# HYDRA_V4_RECOVERY.net
KiCad netlist of a schematic drawn in Altium Designer
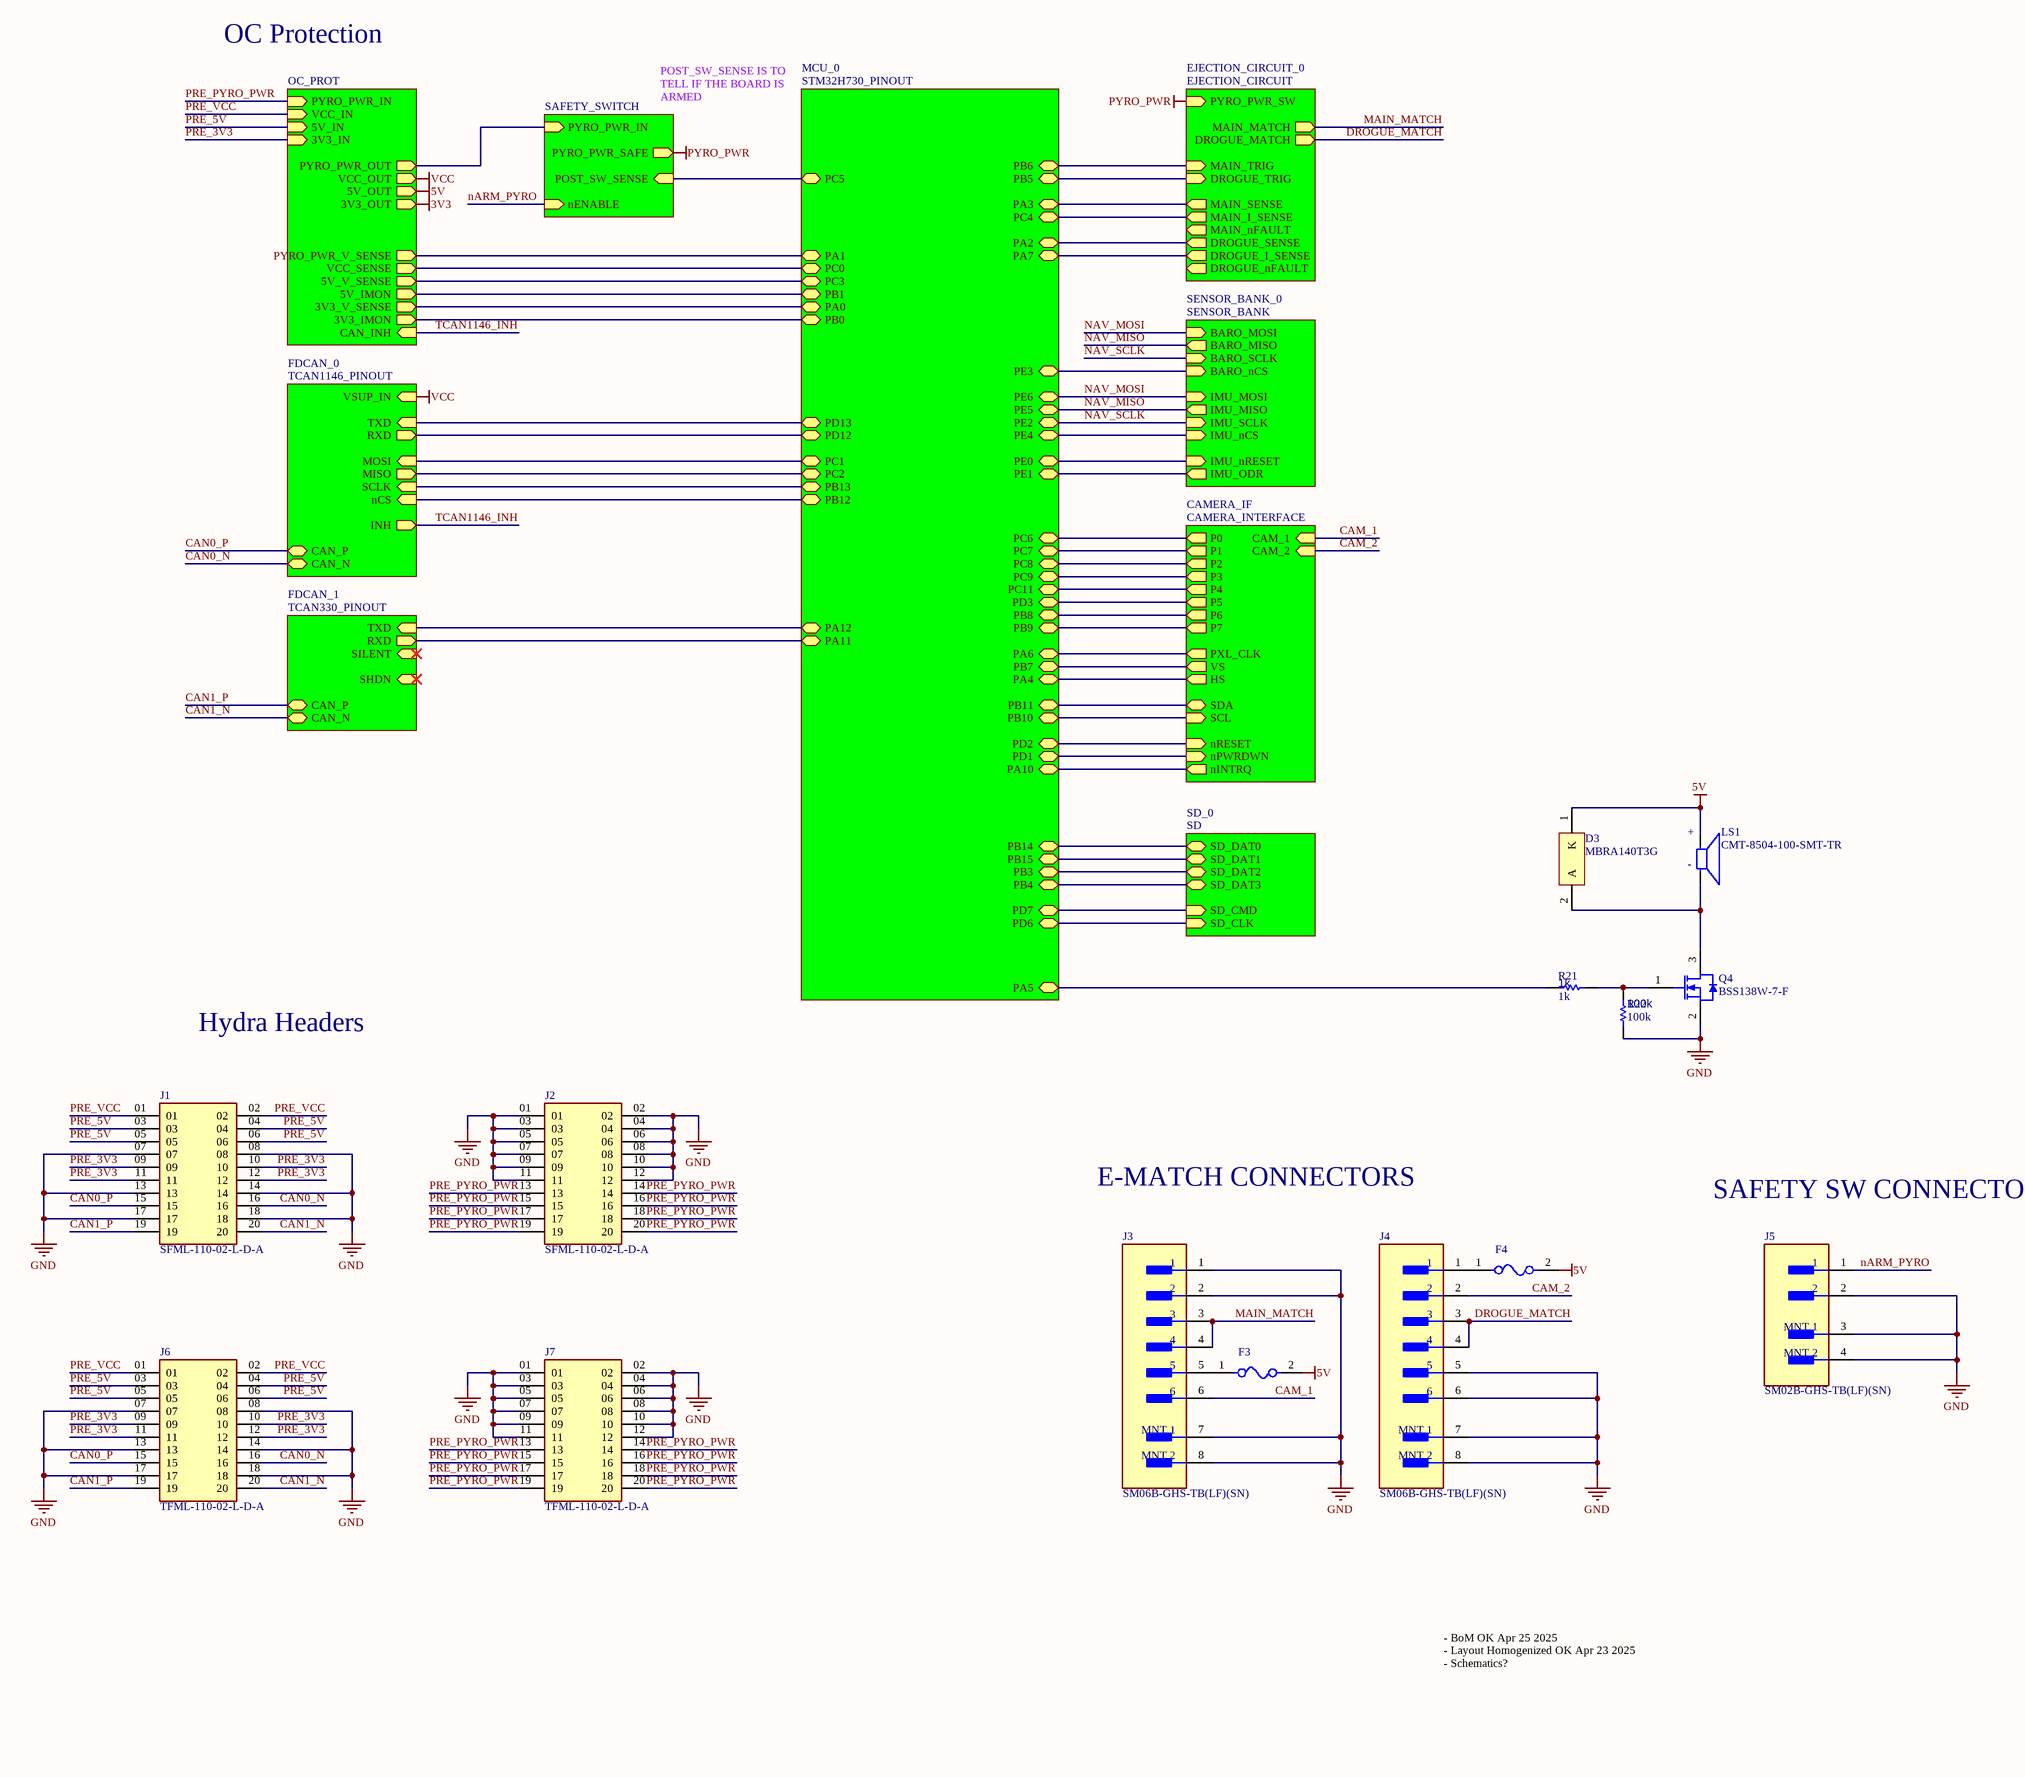
[diagram p0: HYDRA_V4_RECOVERY.SchDoc]

(export (version "E")
  (design (tool "Eeschema 10.0.6"))
  (components
    (comp (ref "D3")
      (value "MBRA140T3G")
      (footprint "ONSC-SMA-2-403D-02_V")
      (description "Schottky Power Rectifier, 2-Pin SMA, Pb-Free, Tape and Reel")
      (fields (field (name "MANUFACTURER") "On Semiconductor"))
      (libsource (lib "Altium Content Vault") (part "ONSC-D-K1A2-2_A"))
    )
    (comp (ref "F3")
      (value "MF-FSMF050X-2")
      (footprint "FP-MF-FSMF-MFG")
      (description "PTC RESET FUSE 6V 500MA 0603")
      (fields
        (field (name "MANUFACTURER") "Bourns Inc.")
        (field (name "OCTOPART") "https://octopart.com/mf-fsmf050x-2-bourns-10470804")
      )
      (libsource (lib "Altium Content Vault") (part "5bcf9b9f640e542cf0359d10258e979"))
    )
    (comp (ref "F4")
      (value "MF-FSMF050X-2")
      (footprint "FP-MF-FSMF-MFG")
      (description "PTC RESET FUSE 6V 500MA 0603")
      (fields
        (field (name "MANUFACTURER") "Bourns Inc.")
        (field (name "OCTOPART") "https://octopart.com/mf-fsmf050x-2-bourns-10470804")
      )
      (libsource (lib "Altium Content Vault") (part "5bcf9b9f640e542cf0359d10258e979"))
    )
    (comp (ref "J1")
      (value "SFML-110-02-L-D-A")
      (footprint "SFML-110-02-L-D-A-Footprint-1")
      (libsource (lib "Space Concordia") (part "SFML-110-02-L-D-A"))
    )
    (comp (ref "J2")
      (value "SFML-110-02-L-D-A")
      (footprint "SFML-110-02-L-D-A-Footprint-1")
      (libsource (lib "Space Concordia") (part "SFML-110-02-L-D-A"))
    )
    (comp (ref "J3")
      (value "SM06B-GHS-TB(LF)(SN)")
      (footprint "FP-SM06B-GHS-TB_LF_SN-MFG")
      (description "Conn Shrouded Header HDR 6 POS 1.25mm Solder RA Side Entry SMD T/R")
      (libsource (lib "Space Concordia") (part "ed24c53d9ba001d1a2a686240a95171"))
    )
    (comp (ref "J4")
      (value "SM06B-GHS-TB(LF)(SN)")
      (footprint "FP-SM06B-GHS-TB_LF_SN-MFG")
      (description "Conn Shrouded Header HDR 6 POS 1.25mm Solder RA Side Entry SMD T/R")
      (libsource (lib "Space Concordia") (part "ed24c53d9ba001d1a2a686240a95171"))
    )
    (comp (ref "J5")
      (value "SM02B-GHS-TB(LF)(SN)")
      (footprint "FP-SM02B-GHS-TB_LF_SN-MFG")
      (description "MCU 32-bit LPC1800 ARM Cortex M3 RISC 768KB Flash 3.3V 100-Pin TFBGA Tray")
      (libsource (lib "Space Concordia") (part "56ec3178a87b3978bdc1b3682cd516a"))
    )
    (comp (ref "J6")
      (value "TFML-110-02-L-D-A")
      (footprint "TFML-110-02-L-D-A-Footprint-1")
      (description "Board Connector, 20 Contact(s), 2 Row(s), Male, Straight, Surface Mount Terminal")
      (libsource (lib "Space Concordia") (part "TFML-110-02-L-D-A"))
    )
    (comp (ref "J7")
      (value "TFML-110-02-L-D-A")
      (footprint "TFML-110-02-L-D-A-Footprint-1")
      (description "Board Connector, 20 Contact(s), 2 Row(s), Male, Straight, Surface Mount Terminal")
      (libsource (lib "Space Concordia") (part "TFML-110-02-L-D-A"))
    )
    (comp (ref "LS1")
      (value "CMT-8504-100-SMT-TR")
      (footprint "CMT-8504-100-SMT-TR-Footprint-1")
      (description "8.5 mm, 5 Vo-p, 100 dB, Surface Mount (SMT), Magnetic Audio Transducer Buzzer")
      (libsource (lib "Space Concordia") (part "CMT-8504-100-SMT-TR"))
    )
    (comp (ref "Q4")
      (value "BSS138W-7-F")
      (footprint "DIOD-SOT323-3_V")
      (fields (field (name "MANUFACTURER") "DiodesIncorporated"))
      (libsource (lib "Altium Content Vault") (part "NEMOS-GSD-3"))
    )
    (comp (ref "R21")
      (value "1k")
      (footprint "R0603B")
      (description "Resistor")
      (fields (field (name "ALTIUM_VALUE") "1k"))
      (libsource (lib "Space Concordia") (part "Resistor"))
    )
    (comp (ref "R22")
      (value "100k")
      (footprint "R0603B")
      (description "Resistor")
      (fields (field (name "ALTIUM_VALUE") "100k"))
      (libsource (lib "Space Concordia") (part "Resistor"))
    )
  )
  (nets
    (net (code "6") (name "/CAM_1") (class "Default")
      (node (ref "J3") (pin "6") (pinfunction "6_6") (pintype "passive"))
    )
    (net (code "7") (name "/CAM_2") (class "Default")
      (node (ref "J4") (pin "2") (pinfunction "2_2") (pintype "passive"))
    )
    (net (code "8") (name "/CAN0_N") (class "Default")
      (node (ref "J1") (pin "16") (pinfunction "16_16") (pintype "passive"))
      (node (ref "J6") (pin "16") (pinfunction "16_16") (pintype "passive"))
    )
    (net (code "9") (name "/CAN0_P") (class "Default")
      (node (ref "J1") (pin "15") (pinfunction "15_15") (pintype "passive"))
      (node (ref "J6") (pin "15") (pinfunction "15_15") (pintype "passive"))
    )
    (net (code "10") (name "/CAN1_N") (class "Default")
      (node (ref "J1") (pin "20") (pinfunction "20_20") (pintype "passive"))
      (node (ref "J6") (pin "20") (pinfunction "20_20") (pintype "passive"))
    )
    (net (code "11") (name "/CAN1_P") (class "Default")
      (node (ref "J1") (pin "19") (pinfunction "19_19") (pintype "passive"))
      (node (ref "J6") (pin "19") (pinfunction "19_19") (pintype "passive"))
    )
    (net (code "13") (name "/DROGUE_MATCH") (class "Default")
      (node (ref "J4") (pin "3") (pinfunction "3_3") (pintype "passive"))
      (node (ref "J4") (pin "4") (pinfunction "4_4") (pintype "passive"))
    )
    (net (code "22") (name "/MAIN_MATCH") (class "Default")
      (node (ref "J3") (pin "3") (pinfunction "3_3") (pintype "passive"))
      (node (ref "J3") (pin "4") (pinfunction "4_4") (pintype "passive"))
    )
    (net (code "39") (name "/PA5") (class "Default")
      (node (ref "R21") (pin "2") (pinfunction "2_2") (pintype "passive"))
    )
    (net (code "55") (name "/PRE_3V3") (class "Default")
      (node (ref "J1") (pin "09") (pinfunction "09_09") (pintype "passive"))
      (node (ref "J1") (pin "10") (pinfunction "10_10") (pintype "passive"))
      (node (ref "J1") (pin "11") (pinfunction "11_11") (pintype "passive"))
      (node (ref "J1") (pin "12") (pinfunction "12_12") (pintype "passive"))
      (node (ref "J6") (pin "09") (pinfunction "09_09") (pintype "passive"))
      (node (ref "J6") (pin "10") (pinfunction "10_10") (pintype "passive"))
      (node (ref "J6") (pin "11") (pinfunction "11_11") (pintype "passive"))
      (node (ref "J6") (pin "12") (pinfunction "12_12") (pintype "passive"))
    )
    (net (code "56") (name "/PRE_5V") (class "Default")
      (node (ref "J1") (pin "03") (pinfunction "03_03") (pintype "passive"))
      (node (ref "J1") (pin "04") (pinfunction "04_04") (pintype "passive"))
      (node (ref "J1") (pin "05") (pinfunction "05_05") (pintype "passive"))
      (node (ref "J1") (pin "06") (pinfunction "06_06") (pintype "passive"))
      (node (ref "J6") (pin "03") (pinfunction "03_03") (pintype "passive"))
      (node (ref "J6") (pin "04") (pinfunction "04_04") (pintype "passive"))
      (node (ref "J6") (pin "05") (pinfunction "05_05") (pintype "passive"))
      (node (ref "J6") (pin "06") (pinfunction "06_06") (pintype "passive"))
    )
    (net (code "57") (name "/PRE_PYRO_PWR") (class "Default")
      (node (ref "J2") (pin "13") (pinfunction "13_13") (pintype "passive"))
      (node (ref "J2") (pin "14") (pinfunction "14_14") (pintype "passive"))
      (node (ref "J2") (pin "15") (pinfunction "15_15") (pintype "passive"))
      (node (ref "J2") (pin "16") (pinfunction "16_16") (pintype "passive"))
      (node (ref "J2") (pin "17") (pinfunction "17_17") (pintype "passive"))
      (node (ref "J2") (pin "18") (pinfunction "18_18") (pintype "passive"))
      (node (ref "J2") (pin "19") (pinfunction "19_19") (pintype "passive"))
      (node (ref "J2") (pin "20") (pinfunction "20_20") (pintype "passive"))
      (node (ref "J7") (pin "13") (pinfunction "13_13") (pintype "passive"))
      (node (ref "J7") (pin "14") (pinfunction "14_14") (pintype "passive"))
      (node (ref "J7") (pin "15") (pinfunction "15_15") (pintype "passive"))
      (node (ref "J7") (pin "16") (pinfunction "16_16") (pintype "passive"))
      (node (ref "J7") (pin "17") (pinfunction "17_17") (pintype "passive"))
      (node (ref "J7") (pin "18") (pinfunction "18_18") (pintype "passive"))
      (node (ref "J7") (pin "19") (pinfunction "19_19") (pintype "passive"))
      (node (ref "J7") (pin "20") (pinfunction "20_20") (pintype "passive"))
    )
    (net (code "58") (name "/PRE_VCC") (class "Default")
      (node (ref "J1") (pin "01") (pinfunction "01_01") (pintype "passive"))
      (node (ref "J1") (pin "02") (pinfunction "02_02") (pintype "passive"))
      (node (ref "J6") (pin "01") (pinfunction "01_01") (pintype "passive"))
      (node (ref "J6") (pin "02") (pinfunction "02_02") (pintype "passive"))
    )
    (net (code "69") (name "/nARM_PYRO") (class "Default")
      (node (ref "J5") (pin "1") (pinfunction "1_1") (pintype "passive"))
    )
    (net (code "72") (name "5V") (class "Default")
      (node (ref "D3") (pin "1") (pinfunction "K_1") (pintype "passive"))
      (node (ref "F3") (pin "2") (pinfunction "2_2") (pintype "passive"))
      (node (ref "F4") (pin "2") (pinfunction "2_2") (pintype "passive"))
      (node (ref "LS1") (pin "P") (pinfunction "P_P") (pintype "passive"))
    )
    (net (code "73") (name "GND") (class "Default")
      (node (ref "J1") (pin "07") (pinfunction "07_07") (pintype "passive"))
      (node (ref "J1") (pin "08") (pinfunction "08_08") (pintype "passive"))
      (node (ref "J1") (pin "13") (pinfunction "13_13") (pintype "passive"))
      (node (ref "J1") (pin "14") (pinfunction "14_14") (pintype "passive"))
      (node (ref "J1") (pin "17") (pinfunction "17_17") (pintype "passive"))
      (node (ref "J1") (pin "18") (pinfunction "18_18") (pintype "passive"))
      (node (ref "J2") (pin "01") (pinfunction "01_01") (pintype "passive"))
      (node (ref "J2") (pin "02") (pinfunction "02_02") (pintype "passive"))
      (node (ref "J2") (pin "03") (pinfunction "03_03") (pintype "passive"))
      (node (ref "J2") (pin "04") (pinfunction "04_04") (pintype "passive"))
      (node (ref "J2") (pin "05") (pinfunction "05_05") (pintype "passive"))
      (node (ref "J2") (pin "06") (pinfunction "06_06") (pintype "passive"))
      (node (ref "J2") (pin "07") (pinfunction "07_07") (pintype "passive"))
      (node (ref "J2") (pin "08") (pinfunction "08_08") (pintype "passive"))
      (node (ref "J2") (pin "09") (pinfunction "09_09") (pintype "passive"))
      (node (ref "J2") (pin "10") (pinfunction "10_10") (pintype "passive"))
      (node (ref "J2") (pin "11") (pinfunction "11_11") (pintype "passive"))
      (node (ref "J2") (pin "12") (pinfunction "12_12") (pintype "passive"))
      (node (ref "J3") (pin "1") (pinfunction "1_1") (pintype "passive"))
      (node (ref "J3") (pin "2") (pinfunction "2_2") (pintype "passive"))
      (node (ref "J3") (pin "7") (pinfunction "MNT_1_7") (pintype "passive"))
      (node (ref "J3") (pin "8") (pinfunction "MNT_2_8") (pintype "passive"))
      (node (ref "J4") (pin "5") (pinfunction "5_5") (pintype "passive"))
      (node (ref "J4") (pin "6") (pinfunction "6_6") (pintype "passive"))
      (node (ref "J4") (pin "7") (pinfunction "MNT_1_7") (pintype "passive"))
      (node (ref "J4") (pin "8") (pinfunction "MNT_2_8") (pintype "passive"))
      (node (ref "J5") (pin "2") (pinfunction "2_2") (pintype "passive"))
      (node (ref "J5") (pin "3") (pinfunction "MNT_1_3") (pintype "passive"))
      (node (ref "J5") (pin "4") (pinfunction "MNT_2_4") (pintype "passive"))
      (node (ref "J6") (pin "07") (pinfunction "07_07") (pintype "passive"))
      (node (ref "J6") (pin "08") (pinfunction "08_08") (pintype "passive"))
      (node (ref "J6") (pin "13") (pinfunction "13_13") (pintype "passive"))
      (node (ref "J6") (pin "14") (pinfunction "14_14") (pintype "passive"))
      (node (ref "J6") (pin "17") (pinfunction "17_17") (pintype "passive"))
      (node (ref "J6") (pin "18") (pinfunction "18_18") (pintype "passive"))
      (node (ref "J7") (pin "01") (pinfunction "01_01") (pintype "passive"))
      (node (ref "J7") (pin "02") (pinfunction "02_02") (pintype "passive"))
      (node (ref "J7") (pin "03") (pinfunction "03_03") (pintype "passive"))
      (node (ref "J7") (pin "04") (pinfunction "04_04") (pintype "passive"))
      (node (ref "J7") (pin "05") (pinfunction "05_05") (pintype "passive"))
      (node (ref "J7") (pin "06") (pinfunction "06_06") (pintype "passive"))
      (node (ref "J7") (pin "07") (pinfunction "07_07") (pintype "passive"))
      (node (ref "J7") (pin "08") (pinfunction "08_08") (pintype "passive"))
      (node (ref "J7") (pin "09") (pinfunction "09_09") (pintype "passive"))
      (node (ref "J7") (pin "10") (pinfunction "10_10") (pintype "passive"))
      (node (ref "J7") (pin "11") (pinfunction "11_11") (pintype "passive"))
      (node (ref "J7") (pin "12") (pinfunction "12_12") (pintype "passive"))
      (node (ref "Q4") (pin "2") (pinfunction "S_2") (pintype "passive"))
      (node (ref "R22") (pin "2") (pinfunction "2_2") (pintype "passive"))
    )
    (net (code "74") (name "Net-(D3-A)") (class "Default")
      (node (ref "D3") (pin "2") (pinfunction "A_2") (pintype "passive"))
      (node (ref "LS1") (pin "N") (pinfunction "N_N") (pintype "passive"))
      (node (ref "Q4") (pin "3") (pinfunction "D_3") (pintype "passive"))
    )
    (net (code "75") (name "Net-(F3-Pad1)") (class "Default")
      (node (ref "F3") (pin "1") (pinfunction "1_1") (pintype "passive"))
      (node (ref "J3") (pin "5") (pinfunction "5_5") (pintype "passive"))
    )
    (net (code "76") (name "Net-(F4-Pad1)") (class "Default")
      (node (ref "F4") (pin "1") (pinfunction "1_1") (pintype "passive"))
      (node (ref "J4") (pin "1") (pinfunction "1_1") (pintype "passive"))
    )
    (net (code "77") (name "Net-(Q4-G)") (class "Default")
      (node (ref "Q4") (pin "1") (pinfunction "G_1") (pintype "passive"))
      (node (ref "R21") (pin "1") (pinfunction "1_1") (pintype "passive"))
      (node (ref "R22") (pin "1") (pinfunction "1_1") (pintype "passive"))
    )
  )
)
